# main-oscillator.net
KiCad netlist of a schematic drawn in EAGLE
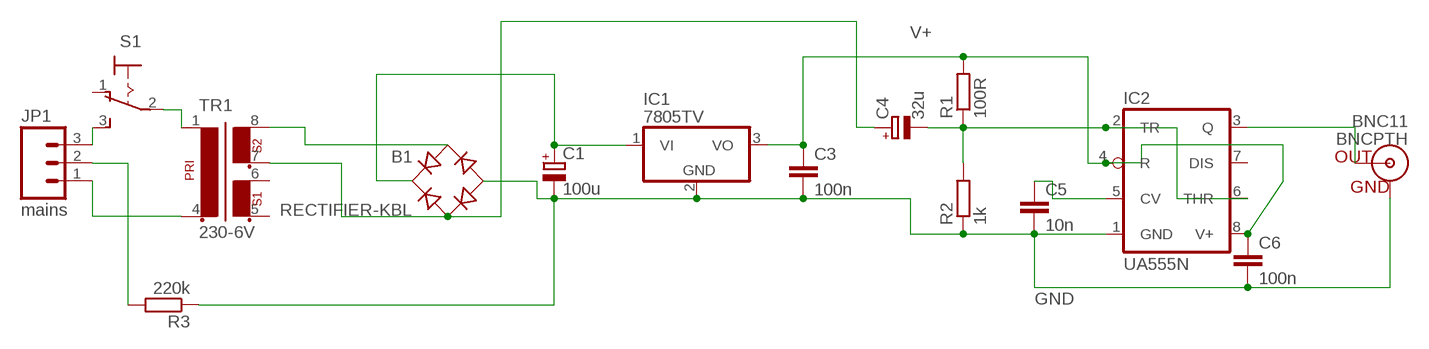
[diagram p0: schematic, sheet 1]

(export (version "E")
  (design (tool "Eeschema 10.0.6"))
  (components
    (comp (ref "B1")
      (value "RECTIFIER-KBL")
      (footprint "eagle-import:B-DIL")
      (libsource (lib "eagle-import") (part "B-DIL"))
    )
    (comp (ref "BNC11")
      (value "BNCPTH")
      (footprint "eagle-import:BNC")
      (libsource (lib "eagle-import") (part "BNCPTH"))
    )
    (comp (ref "C1")
      (value "100u")
      (footprint "eagle-import:E2,5-7")
      (libsource (lib "eagle-import") (part "CPOL-EUE2.5-7"))
    )
    (comp (ref "C3")
      (value "100n")
      (footprint "eagle-import:C050-024X044")
      (libsource (lib "eagle-import") (part "resistor_C-EU050-024X044"))
    )
    (comp (ref "C4")
      (value "32u")
      (footprint "eagle-import:E5-13")
      (libsource (lib "eagle-import") (part "CPOL-EUE5-13"))
    )
    (comp (ref "C5")
      (value "10n")
      (footprint "eagle-import:C025-025X050")
      (libsource (lib "eagle-import") (part "C-EU025-025X050"))
    )
    (comp (ref "C6")
      (value "100n")
      (footprint "eagle-import:C050-024X044")
      (libsource (lib "eagle-import") (part "resistor_C-EU050-024X044"))
    )
    (comp (ref "IC1")
      (value "7805TV")
      (footprint "eagle-import:TO220V")
      (libsource (lib "eagle-import") (part "78TV05"))
    )
    (comp (ref "IC2")
      (value "UA555N")
      (footprint "eagle-import:DIL08")
      (libsource (lib "eagle-import") (part "555NUA"))
    )
    (comp (ref "JP1")
      (value "mains")
      (footprint "eagle-import:SCREWTERMINAL-5MM-3")
      (libsource (lib "eagle-import") (part "M03-SCREW-5MM"))
    )
    (comp (ref "R1")
      (value "100R")
      (footprint "eagle-import:0207_10")
      (libsource (lib "eagle-import") (part "R-EU_0207/10"))
    )
    (comp (ref "R2")
      (value "1k")
      (footprint "eagle-import:0207_10")
      (libsource (lib "eagle-import") (part "R-EU_0207/10"))
    )
    (comp (ref "R3")
      (value "220k")
      (footprint "eagle-import:0207_10")
      (libsource (lib "eagle-import") (part "R-EU_0207/10"))
    )
    (comp (ref "S1")
      (value "320-916")
      (footprint "eagle-import:320-916")
      (libsource (lib "eagle-import") (part "320-916"))
    )
    (comp (ref "TR1")
      (value "230-6V")
      (footprint "eagle-import:EE20-2")
      (libsource (lib "eagle-import") (part "EE20-2"))
    )
  )
  (nets
    (net (code "1") (name "/GND") (class "Default")
      (node (ref "B1") (pin "-") (pinfunction "-_-") (pintype "passive"))
      (node (ref "BNC11") (pin "GND") (pinfunction "GND_GND") (pintype "bidirectional"))
      (node (ref "C1") (pin "-") (pinfunction "-_-") (pintype "passive"))
      (node (ref "C3") (pin "2") (pinfunction "2_2") (pintype "passive"))
      (node (ref "C5") (pin "2") (pinfunction "2_2") (pintype "passive"))
      (node (ref "C6") (pin "2") (pinfunction "2_2") (pintype "passive"))
      (node (ref "IC1") (pin "2") (pinfunction "GND_2") (pintype "passive"))
      (node (ref "IC2") (pin "1") (pinfunction "GND_1") (pintype "power_in"))
      (node (ref "R2") (pin "1") (pinfunction "1_1") (pintype "passive"))
      (node (ref "R3") (pin "1") (pinfunction "1_1") (pintype "passive"))
    )
    (net (code "2") (name "/V+") (class "Default")
      (node (ref "C3") (pin "1") (pinfunction "1_1") (pintype "passive"))
      (node (ref "C6") (pin "1") (pinfunction "1_1") (pintype "passive"))
      (node (ref "IC1") (pin "3") (pinfunction "VO_3") (pintype "passive"))
      (node (ref "IC2") (pin "4") (pinfunction "R_4") (pintype "input"))
      (node (ref "IC2") (pin "8") (pinfunction "V+_8") (pintype "power_in"))
      (node (ref "R1") (pin "2") (pinfunction "2_2") (pintype "passive"))
    )
    (net (code "3") (name "Net-(BNC11-OUT)") (class "Default")
      (node (ref "BNC11") (pin "S") (pinfunction "OUT_S") (pintype "bidirectional"))
      (node (ref "IC2") (pin "3") (pinfunction "Q_3") (pintype "output"))
    )
    (net (code "4") (name "Net-(IC1-VI)") (class "Default")
      (node (ref "B1") (pin "+") (pinfunction "+_+") (pintype "passive"))
      (node (ref "C1") (pin "+") (pinfunction "+_+") (pintype "passive"))
      (node (ref "IC1") (pin "1") (pinfunction "VI_1") (pintype "input"))
    )
    (net (code "5") (name "Net-(IC2-CV)") (class "Default")
      (node (ref "C5") (pin "1") (pinfunction "1_1") (pintype "passive"))
      (node (ref "IC2") (pin "5") (pinfunction "CV_5") (pintype "input"))
    )
    (net (code "6") (name "Net-(IC2-THR)") (class "Default")
      (node (ref "C4") (pin "-") (pinfunction "-_-") (pintype "passive"))
      (node (ref "IC2") (pin "2") (pinfunction "TR_2") (pintype "input"))
      (node (ref "IC2") (pin "6") (pinfunction "THR_6") (pintype "input"))
      (node (ref "R1") (pin "1") (pinfunction "1_1") (pintype "passive"))
      (node (ref "R2") (pin "2") (pinfunction "2_2") (pintype "passive"))
    )
    (net (code "7") (name "Net-(JP1-Pad2)") (class "Default")
      (node (ref "JP1") (pin "2") (pinfunction "2_2") (pintype "passive"))
      (node (ref "R3") (pin "2") (pinfunction "2_2") (pintype "passive"))
    )
    (net (code "8") (name "Net-(S1-P)") (class "Default")
      (node (ref "S1") (pin "2") (pinfunction "P_2") (pintype "passive"))
      (node (ref "TR1") (pin "1") (pinfunction "1_1") (pintype "passive"))
    )
    (net (code "9") (name "Net-(S1-S)") (class "Default")
      (node (ref "JP1") (pin "3") (pinfunction "3_3") (pintype "passive"))
      (node (ref "S1") (pin "3") (pinfunction "S_3") (pintype "passive"))
    )
    (net (code "10") (name "Net-(TR1-2)") (class "Default")
      (node (ref "JP1") (pin "1") (pinfunction "1_1") (pintype "passive"))
      (node (ref "TR1") (pin "4") (pinfunction "2_4") (pintype "passive"))
    )
    (net (code "11") (name "Net-(TR1-5)") (class "Default")
      (node (ref "B1") (pin "AC2") (pinfunction "AC2_AC2") (pintype "passive"))
      (node (ref "C4") (pin "+") (pinfunction "+_+") (pintype "passive"))
      (node (ref "TR1") (pin "7") (pinfunction "5_7") (pintype "passive"))
    )
    (net (code "12") (name "Net-(TR1-6)") (class "Default")
      (node (ref "B1") (pin "AC1") (pinfunction "AC1_AC1") (pintype "passive"))
      (node (ref "TR1") (pin "8") (pinfunction "6_8") (pintype "passive"))
    )
    (net (code "13") (name "unconnected-(IC2-DIS-Pad7)") (class "Default")
      (node (ref "IC2") (pin "7") (pinfunction "DIS_7") (pintype "input"))
    )
    (net (code "14") (name "unconnected-(S1-O-Pad1)") (class "Default")
      (node (ref "S1") (pin "1") (pinfunction "O_1") (pintype "passive"))
    )
    (net (code "15") (name "unconnected-(TR1-3-Pad5)") (class "Default")
      (node (ref "TR1") (pin "5") (pinfunction "3_5") (pintype "passive"))
    )
    (net (code "16") (name "unconnected-(TR1-4-Pad6)") (class "Default")
      (node (ref "TR1") (pin "6") (pinfunction "4_6") (pintype "passive"))
    )
  )
)
